# micron_P2.net
KiCad netlist of a schematic drawn in Altium Designer
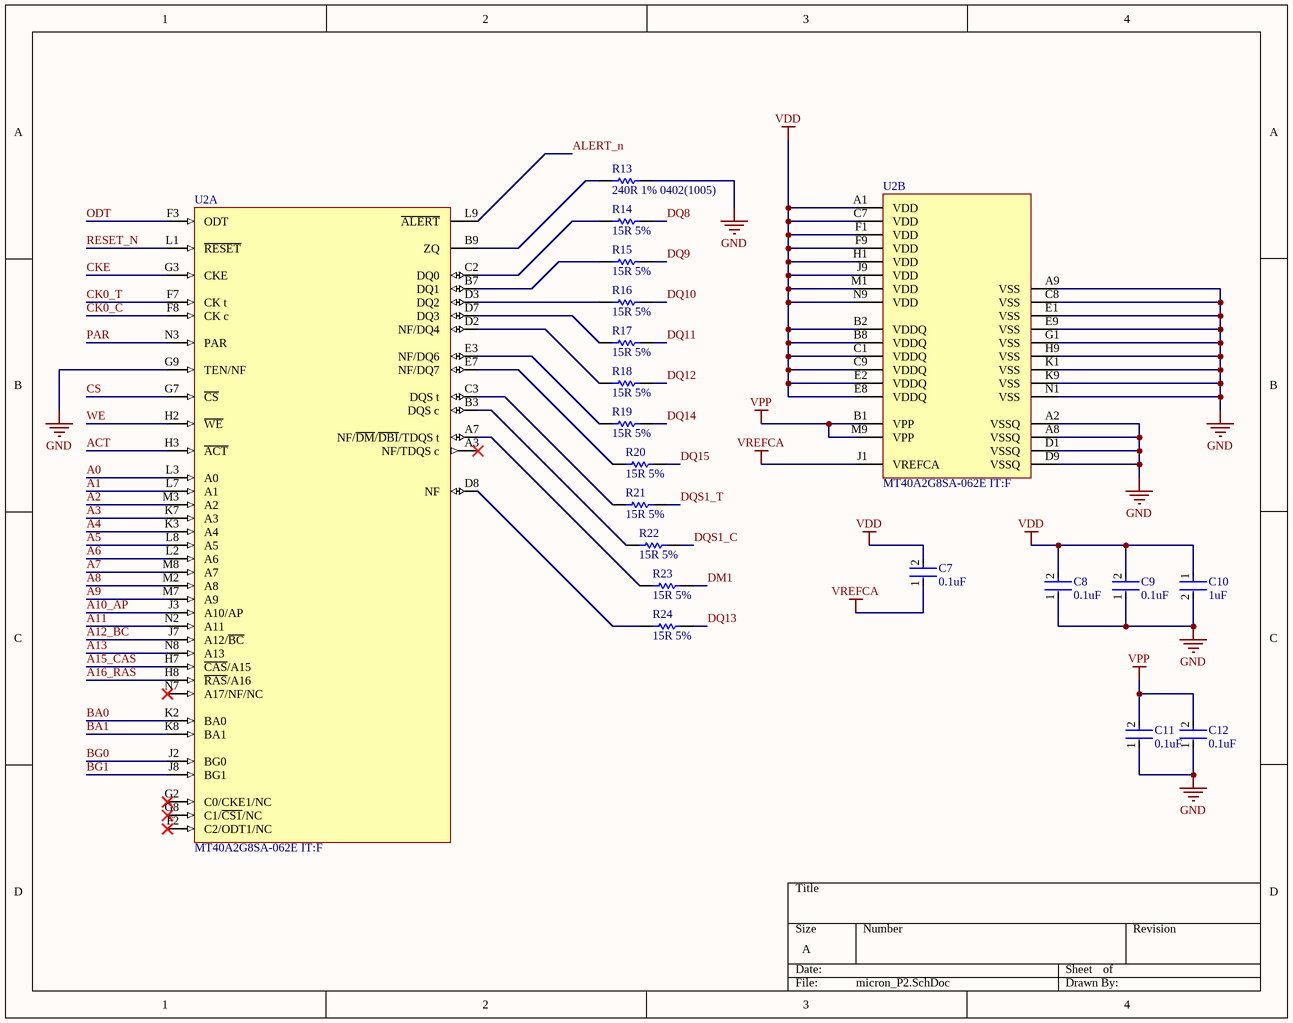
[diagram p0: micron_P2.SchDoc]

(export (version "E")
  (design (tool "Eeschema 10.0.6"))
  (components
    (comp (ref "C7")
      (value "0.1uF")
      (footprint "FP-GRM15-MFG")
      (description "CAP CER 0.1UF 16V X7R 0402")
      (fields (field (name "MANUFACTURER PART NUMBER") "GRM155R71C104KA88D") (field (name "TOLERANCE") "10%"))
      (libsource (lib "Altium Content Vault") (part "236180d848d6139a670b325ea6854c9"))
    )
    (comp (ref "C8")
      (value "0.1uF")
      (footprint "FP-GRM15-MFG")
      (description "CAP CER 0.1UF 16V X7R 0402")
      (fields (field (name "MANUFACTURER PART NUMBER") "GRM155R71C104KA88D") (field (name "TOLERANCE") "10%"))
      (libsource (lib "Altium Content Vault") (part "236180d848d6139a670b325ea6854c9"))
    )
    (comp (ref "C9")
      (value "0.1uF")
      (footprint "FP-GRM15-MFG")
      (description "CAP CER 0.1UF 16V X7R 0402")
      (fields (field (name "MANUFACTURER PART NUMBER") "GRM155R71C104KA88D") (field (name "TOLERANCE") "10%"))
      (libsource (lib "Altium Content Vault") (part "236180d848d6139a670b325ea6854c9"))
    )
    (comp (ref "C10")
      (value "1uF")
      (footprint "FP-CL511-IPC_C")
      (description "Cap Ceramic 1uF 10V X5R ±10% SMD 0402 +85°C Paper T/R")
      (fields (field (name "TOLERANCE") "10%"))
      (libsource (lib "Altium Content Vault") (part "b4654b650e69147ec39a6b967a45e02"))
    )
    (comp (ref "C11")
      (value "0.1uF")
      (footprint "FP-GRM15-MFG")
      (description "CAP CER 0.1UF 16V X7R 0402")
      (fields (field (name "MANUFACTURER PART NUMBER") "GRM155R71C104KA88D") (field (name "TOLERANCE") "10%"))
      (libsource (lib "Altium Content Vault") (part "236180d848d6139a670b325ea6854c9"))
    )
    (comp (ref "C12")
      (value "0.1uF")
      (footprint "FP-GRM15-MFG")
      (description "CAP CER 0.1UF 16V X7R 0402")
      (fields (field (name "MANUFACTURER PART NUMBER") "GRM155R71C104KA88D") (field (name "TOLERANCE") "10%"))
      (libsource (lib "Altium Content Vault") (part "236180d848d6139a670b325ea6854c9"))
    )
    (comp (ref "R13")
      (value "240R 1% 0402(1005)")
      (footprint "RESC0402(1005)_L")
      (description "240R 0.063W 1% 0402 (1005 Metric)  SMD")
      (fields (field (name "POWER") "0.063 W") (field (name "TOLERANCE") "1 %"))
      (libsource (lib "Altium Content Vault") (part "RES"))
    )
    (comp (ref "R14")
      (value "15R 5%")
      (footprint "RESC1005X40X25LL05T10")
      (fields (field (name "MANUFACTURER") "Yageo / Phycomp") (field (name "PART NUMBER") "RC0402FR-0715RL"))
      (libsource (lib "Altium Content Vault") (part "RES"))
    )
    (comp (ref "R15")
      (value "15R 5%")
      (footprint "RESC1005X40X25LL05T10")
      (fields (field (name "MANUFACTURER") "Yageo / Phycomp") (field (name "PART NUMBER") "RC0402FR-0715RL"))
      (libsource (lib "Altium Content Vault") (part "RES"))
    )
    (comp (ref "R16")
      (value "15R 5%")
      (footprint "RESC1005X40X25LL05T10")
      (fields (field (name "MANUFACTURER") "Yageo / Phycomp") (field (name "PART NUMBER") "RC0402FR-0715RL"))
      (libsource (lib "Altium Content Vault") (part "RES"))
    )
    (comp (ref "R17")
      (value "15R 5%")
      (footprint "RESC1005X40X25LL05T10")
      (fields (field (name "MANUFACTURER") "Yageo / Phycomp") (field (name "PART NUMBER") "RC0402FR-0715RL"))
      (libsource (lib "Altium Content Vault") (part "RES"))
    )
    (comp (ref "R18")
      (value "15R 5%")
      (footprint "RESC1005X40X25LL05T10")
      (fields (field (name "MANUFACTURER") "Yageo / Phycomp") (field (name "PART NUMBER") "RC0402FR-0715RL"))
      (libsource (lib "Altium Content Vault") (part "RES"))
    )
    (comp (ref "R19")
      (value "15R 5%")
      (footprint "RESC1005X40X25LL05T10")
      (fields (field (name "MANUFACTURER") "Yageo / Phycomp") (field (name "PART NUMBER") "RC0402FR-0715RL"))
      (libsource (lib "Altium Content Vault") (part "RES"))
    )
    (comp (ref "R20")
      (value "15R 5%")
      (footprint "RESC1005X40X25LL05T10")
      (fields (field (name "MANUFACTURER") "Yageo / Phycomp") (field (name "PART NUMBER") "RC0402FR-0715RL"))
      (libsource (lib "Altium Content Vault") (part "RES"))
    )
    (comp (ref "R21")
      (value "15R 5%")
      (footprint "RESC1005X40X25LL05T10")
      (fields (field (name "MANUFACTURER") "Yageo / Phycomp") (field (name "PART NUMBER") "RC0402FR-0715RL"))
      (libsource (lib "Altium Content Vault") (part "RES"))
    )
    (comp (ref "R22")
      (value "15R 5%")
      (footprint "RESC1005X40X25LL05T10")
      (fields (field (name "MANUFACTURER") "Yageo / Phycomp") (field (name "PART NUMBER") "RC0402FR-0715RL"))
      (libsource (lib "Altium Content Vault") (part "RES"))
    )
    (comp (ref "R23")
      (value "15R 5%")
      (footprint "RESC1005X40X25LL05T10")
      (fields (field (name "MANUFACTURER") "Yageo / Phycomp") (field (name "PART NUMBER") "RC0402FR-0715RL"))
      (libsource (lib "Altium Content Vault") (part "RES"))
    )
    (comp (ref "R24")
      (value "15R 5%")
      (footprint "RESC1005X40X25LL05T10")
      (fields (field (name "MANUFACTURER") "Yageo / Phycomp") (field (name "PART NUMBER") "RC0402FR-0715RL"))
      (libsource (lib "Altium Content Vault") (part "RES"))
    )
    (comp (ref "U2")
      (value "MT40A2G8SA-062E IT:F")
      (footprint "SA_MFG")
      (description "DRAMChip DDR4 SDRAM 16Gbit 2Gx8 1.2V 78-Pin FBGA Tray")
      (libsource (lib "Altium Content Vault") (part "d28cb998757b614ee3280f10a38a3b1"))
    )
  )
  (nets
    (net (code "1") (name "/A0") (class "Default")
      (node (ref "U2") (pin "L3") (pinfunction "A0_L3") (pintype "input"))
    )
    (net (code "2") (name "/A1") (class "Default")
      (node (ref "U2") (pin "L7") (pinfunction "A1_L7") (pintype "input"))
    )
    (net (code "3") (name "/A2") (class "Default")
      (node (ref "U2") (pin "M3") (pinfunction "A2_M3") (pintype "input"))
    )
    (net (code "4") (name "/A3") (class "Default")
      (node (ref "U2") (pin "K7") (pinfunction "A3_K7") (pintype "input"))
    )
    (net (code "5") (name "/A4") (class "Default")
      (node (ref "U2") (pin "K3") (pinfunction "A4_K3") (pintype "input"))
    )
    (net (code "6") (name "/A5") (class "Default")
      (node (ref "U2") (pin "L8") (pinfunction "A5_L8") (pintype "input"))
    )
    (net (code "7") (name "/A6") (class "Default")
      (node (ref "U2") (pin "L2") (pinfunction "A6_L2") (pintype "input"))
    )
    (net (code "8") (name "/A7") (class "Default")
      (node (ref "U2") (pin "M8") (pinfunction "A7_M8") (pintype "input"))
    )
    (net (code "9") (name "/A8") (class "Default")
      (node (ref "U2") (pin "M2") (pinfunction "A8_M2") (pintype "input"))
    )
    (net (code "10") (name "/A9") (class "Default")
      (node (ref "U2") (pin "M7") (pinfunction "A9_M7") (pintype "input"))
    )
    (net (code "11") (name "/A10_AP") (class "Default")
      (node (ref "U2") (pin "J3") (pinfunction "A10/AP_J3") (pintype "input"))
    )
    (net (code "12") (name "/A11") (class "Default")
      (node (ref "U2") (pin "N2") (pinfunction "A11_N2") (pintype "input"))
    )
    (net (code "13") (name "/A12_BC") (class "Default")
      (node (ref "U2") (pin "J7") (pinfunction "A12/~{BC}_J7") (pintype "input"))
    )
    (net (code "14") (name "/A13") (class "Default")
      (node (ref "U2") (pin "N8") (pinfunction "A13_N8") (pintype "input"))
    )
    (net (code "15") (name "/A15_CAS") (class "Default")
      (node (ref "U2") (pin "H7") (pinfunction "~{CAS}/A15_H7") (pintype "input"))
    )
    (net (code "16") (name "/A16_RAS") (class "Default")
      (node (ref "U2") (pin "H8") (pinfunction "~{RAS}/A16_H8") (pintype "input"))
    )
    (net (code "17") (name "/ACT") (class "Default")
      (node (ref "U2") (pin "H3") (pinfunction "~{ACT}_H3") (pintype "input"))
    )
    (net (code "18") (name "/ALERT_n") (class "Default")
      (node (ref "U2") (pin "L9") (pinfunction "~{ALERT}_L9") (pintype "open_collector"))
    )
    (net (code "19") (name "/BA0") (class "Default")
      (node (ref "U2") (pin "K2") (pinfunction "BA0_K2") (pintype "input"))
    )
    (net (code "20") (name "/BA1") (class "Default")
      (node (ref "U2") (pin "K8") (pinfunction "BA1_K8") (pintype "input"))
    )
    (net (code "21") (name "/BG0") (class "Default")
      (node (ref "U2") (pin "J2") (pinfunction "BG0_J2") (pintype "input"))
    )
    (net (code "22") (name "/BG1") (class "Default")
      (node (ref "U2") (pin "J8") (pinfunction "BG1_J8") (pintype "input"))
    )
    (net (code "23") (name "/CK0_C") (class "Default")
      (node (ref "U2") (pin "F8") (pinfunction "CK_c_F8") (pintype "input"))
    )
    (net (code "24") (name "/CK0_T") (class "Default")
      (node (ref "U2") (pin "F7") (pinfunction "CK_t_F7") (pintype "input"))
    )
    (net (code "25") (name "/CKE") (class "Default")
      (node (ref "U2") (pin "G3") (pinfunction "CKE_G3") (pintype "input"))
    )
    (net (code "26") (name "/CS") (class "Default")
      (node (ref "U2") (pin "G7") (pinfunction "~{CS}_G7") (pintype "input"))
    )
    (net (code "27") (name "/DM1") (class "Default")
      (node (ref "R23") (pin "2") (pinfunction "2_2") (pintype "passive"))
    )
    (net (code "28") (name "/DQ8") (class "Default")
      (node (ref "R14") (pin "2") (pinfunction "2_2") (pintype "passive"))
    )
    (net (code "29") (name "/DQ9") (class "Default")
      (node (ref "R15") (pin "2") (pinfunction "2_2") (pintype "passive"))
    )
    (net (code "30") (name "/DQ10") (class "Default")
      (node (ref "R16") (pin "2") (pinfunction "2_2") (pintype "passive"))
    )
    (net (code "31") (name "/DQ11") (class "Default")
      (node (ref "R17") (pin "2") (pinfunction "2_2") (pintype "passive"))
    )
    (net (code "32") (name "/DQ12") (class "Default")
      (node (ref "R18") (pin "2") (pinfunction "2_2") (pintype "passive"))
    )
    (net (code "33") (name "/DQ13") (class "Default")
      (node (ref "R24") (pin "2") (pinfunction "2_2") (pintype "passive"))
    )
    (net (code "34") (name "/DQ14") (class "Default")
      (node (ref "R19") (pin "2") (pinfunction "2_2") (pintype "passive"))
    )
    (net (code "35") (name "/DQ15") (class "Default")
      (node (ref "R20") (pin "2") (pinfunction "2_2") (pintype "passive"))
    )
    (net (code "36") (name "/DQS1_C") (class "Default")
      (node (ref "R22") (pin "2") (pinfunction "2_2") (pintype "passive"))
    )
    (net (code "37") (name "/DQS1_T") (class "Default")
      (node (ref "R21") (pin "2") (pinfunction "2_2") (pintype "passive"))
    )
    (net (code "38") (name "/ODT") (class "Default")
      (node (ref "U2") (pin "F3") (pinfunction "ODT_F3") (pintype "input"))
    )
    (net (code "39") (name "/PAR") (class "Default")
      (node (ref "U2") (pin "N3") (pinfunction "PAR_N3") (pintype "input"))
    )
    (net (code "40") (name "/RESET_N") (class "Default")
      (node (ref "U2") (pin "L1") (pinfunction "~{RESET}_L1") (pintype "input"))
    )
    (net (code "41") (name "/WE") (class "Default")
      (node (ref "U2") (pin "H2") (pinfunction "~{WE}_H2") (pintype "input"))
    )
    (net (code "42") (name "GND") (class "Default")
      (node (ref "C10") (pin "2") (pinfunction "2_2") (pintype "passive"))
      (node (ref "C11") (pin "1") (pinfunction "1_1") (pintype "passive"))
      (node (ref "C12") (pin "1") (pinfunction "1_1") (pintype "passive"))
      (node (ref "C8") (pin "1") (pinfunction "1_1") (pintype "passive"))
      (node (ref "C9") (pin "1") (pinfunction "1_1") (pintype "passive"))
      (node (ref "R13") (pin "2") (pinfunction "2_2") (pintype "passive"))
      (node (ref "U2") (pin "A2") (pinfunction "VSSQ_A2") (pintype "power_in"))
      (node (ref "U2") (pin "A8") (pinfunction "VSSQ_A8") (pintype "power_in"))
      (node (ref "U2") (pin "A9") (pinfunction "VSS_A9") (pintype "power_in"))
      (node (ref "U2") (pin "C8") (pinfunction "VSS_C8") (pintype "power_in"))
      (node (ref "U2") (pin "D1") (pinfunction "VSSQ_D1") (pintype "power_in"))
      (node (ref "U2") (pin "D9") (pinfunction "VSSQ_D9") (pintype "power_in"))
      (node (ref "U2") (pin "E1") (pinfunction "VSS_E1") (pintype "power_in"))
      (node (ref "U2") (pin "E9") (pinfunction "VSS_E9") (pintype "power_in"))
      (node (ref "U2") (pin "G1") (pinfunction "VSS_G1") (pintype "power_in"))
      (node (ref "U2") (pin "G9") (pinfunction "TEN/NF_G9") (pintype "input"))
      (node (ref "U2") (pin "H9") (pinfunction "VSS_H9") (pintype "power_in"))
      (node (ref "U2") (pin "K1") (pinfunction "VSS_K1") (pintype "power_in"))
      (node (ref "U2") (pin "K9") (pinfunction "VSS_K9") (pintype "power_in"))
      (node (ref "U2") (pin "N1") (pinfunction "VSS_N1") (pintype "power_in"))
    )
    (net (code "43") (name "Net-(U2A-DQ0)") (class "Default")
      (node (ref "R14") (pin "1") (pinfunction "1_1") (pintype "passive"))
      (node (ref "U2") (pin "C2") (pinfunction "DQ0_C2") (pintype "bidirectional"))
    )
    (net (code "44") (name "Net-(U2A-DQ1)") (class "Default")
      (node (ref "R15") (pin "1") (pinfunction "1_1") (pintype "passive"))
      (node (ref "U2") (pin "B7") (pinfunction "DQ1_B7") (pintype "bidirectional"))
    )
    (net (code "45") (name "Net-(U2A-DQ2)") (class "Default")
      (node (ref "R16") (pin "1") (pinfunction "1_1") (pintype "passive"))
      (node (ref "U2") (pin "D3") (pinfunction "DQ2_D3") (pintype "bidirectional"))
    )
    (net (code "46") (name "Net-(U2A-DQ3)") (class "Default")
      (node (ref "R17") (pin "1") (pinfunction "1_1") (pintype "passive"))
      (node (ref "U2") (pin "D7") (pinfunction "DQ3_D7") (pintype "bidirectional"))
    )
    (net (code "47") (name "Net-(U2A-DQS_c)") (class "Default")
      (node (ref "R22") (pin "1") (pinfunction "1_1") (pintype "passive"))
      (node (ref "U2") (pin "B3") (pinfunction "DQS_c_B3") (pintype "bidirectional"))
    )
    (net (code "48") (name "Net-(U2A-DQS_t)") (class "Default")
      (node (ref "R21") (pin "1") (pinfunction "1_1") (pintype "passive"))
      (node (ref "U2") (pin "C3") (pinfunction "DQS_t_C3") (pintype "bidirectional"))
    )
    (net (code "49") (name "Net-(U2A-NF)") (class "Default")
      (node (ref "R24") (pin "1") (pinfunction "1_1") (pintype "passive"))
      (node (ref "U2") (pin "D8") (pinfunction "NF_D8") (pintype "bidirectional"))
    )
    (net (code "50") (name "Net-(U2A-NF{slash}DQ4)") (class "Default")
      (node (ref "R18") (pin "1") (pinfunction "1_1") (pintype "passive"))
      (node (ref "U2") (pin "D2") (pinfunction "NF/DQ4_D2") (pintype "bidirectional"))
    )
    (net (code "51") (name "Net-(U2A-NF{slash}DQ6)") (class "Default")
      (node (ref "R19") (pin "1") (pinfunction "1_1") (pintype "passive"))
      (node (ref "U2") (pin "E3") (pinfunction "NF/DQ6_E3") (pintype "bidirectional"))
    )
    (net (code "52") (name "Net-(U2A-NF{slash}DQ7)") (class "Default")
      (node (ref "R20") (pin "1") (pinfunction "1_1") (pintype "passive"))
      (node (ref "U2") (pin "E7") (pinfunction "NF/DQ7_E7") (pintype "bidirectional"))
    )
    (net (code "53") (name "Net-(U2A-NF{slash}~{DM}{slash}~{DBI}{slash}TDQS_t)") (class "Default")
      (node (ref "R23") (pin "1") (pinfunction "1_1") (pintype "passive"))
      (node (ref "U2") (pin "A7") (pinfunction "NF/~{DM}/~{DBI}/TDQS_t_A7") (pintype "bidirectional"))
    )
    (net (code "54") (name "Net-(U2A-ZQ)") (class "Default")
      (node (ref "R13") (pin "1") (pinfunction "1_1") (pintype "passive"))
      (node (ref "U2") (pin "B9") (pinfunction "ZQ_B9") (pintype "passive"))
    )
    (net (code "55") (name "VDD") (class "Default")
      (node (ref "C10") (pin "1") (pinfunction "1_1") (pintype "passive"))
      (node (ref "C7") (pin "2") (pinfunction "2_2") (pintype "passive"))
      (node (ref "C8") (pin "2") (pinfunction "2_2") (pintype "passive"))
      (node (ref "C9") (pin "2") (pinfunction "2_2") (pintype "passive"))
      (node (ref "U2") (pin "A1") (pinfunction "VDD_A1") (pintype "power_in"))
      (node (ref "U2") (pin "B2") (pinfunction "VDDQ_B2") (pintype "power_in"))
      (node (ref "U2") (pin "B8") (pinfunction "VDDQ_B8") (pintype "power_in"))
      (node (ref "U2") (pin "C1") (pinfunction "VDDQ_C1") (pintype "power_in"))
      (node (ref "U2") (pin "C7") (pinfunction "VDD_C7") (pintype "power_in"))
      (node (ref "U2") (pin "C9") (pinfunction "VDDQ_C9") (pintype "power_in"))
      (node (ref "U2") (pin "E2") (pinfunction "VDDQ_E2") (pintype "power_in"))
      (node (ref "U2") (pin "E8") (pinfunction "VDDQ_E8") (pintype "power_in"))
      (node (ref "U2") (pin "F1") (pinfunction "VDD_F1") (pintype "power_in"))
      (node (ref "U2") (pin "F9") (pinfunction "VDD_F9") (pintype "power_in"))
      (node (ref "U2") (pin "H1") (pinfunction "VDD_H1") (pintype "power_in"))
      (node (ref "U2") (pin "J9") (pinfunction "VDD_J9") (pintype "power_in"))
      (node (ref "U2") (pin "M1") (pinfunction "VDD_M1") (pintype "power_in"))
      (node (ref "U2") (pin "N9") (pinfunction "VDD_N9") (pintype "power_in"))
    )
    (net (code "56") (name "VPP") (class "Default")
      (node (ref "C11") (pin "2") (pinfunction "2_2") (pintype "passive"))
      (node (ref "C12") (pin "2") (pinfunction "2_2") (pintype "passive"))
      (node (ref "U2") (pin "B1") (pinfunction "VPP_B1") (pintype "power_in"))
      (node (ref "U2") (pin "M9") (pinfunction "VPP_M9") (pintype "power_in"))
    )
    (net (code "57") (name "VREFCA") (class "Default")
      (node (ref "C7") (pin "1") (pinfunction "1_1") (pintype "passive"))
      (node (ref "U2") (pin "J1") (pinfunction "VREFCA_J1") (pintype "power_in"))
    )
    (net (code "58") (name "unconnected-(U2A-A17{slash}NF{slash}NC-PadN7)") (class "Default")
      (node (ref "U2") (pin "N7") (pinfunction "A17/NF/NC_N7") (pintype "input+no_connect"))
    )
    (net (code "59") (name "unconnected-(U2A-C0{slash}CKE1{slash}NC-PadG2)") (class "Default")
      (node (ref "U2") (pin "G2") (pinfunction "C0/CKE1/NC_G2") (pintype "input+no_connect"))
    )
    (net (code "60") (name "unconnected-(U2A-C1{slash}~{CS1}{slash}NC-PadG8)") (class "Default")
      (node (ref "U2") (pin "G8") (pinfunction "C1/~{CS1}/NC_G8") (pintype "input+no_connect"))
    )
    (net (code "61") (name "unconnected-(U2A-C2{slash}ODT1{slash}NC-PadF2)") (class "Default")
      (node (ref "U2") (pin "F2") (pinfunction "C2/ODT1/NC_F2") (pintype "input+no_connect"))
    )
    (net (code "62") (name "unconnected-(U2A-NF{slash}TDQS_c-PadA3)") (class "Default")
      (node (ref "U2") (pin "A3") (pinfunction "NF/TDQS_c_A3") (pintype "output+no_connect"))
    )
  )
)
